# tractor_2v3.net
KiCad netlist of a schematic drawn in EAGLE
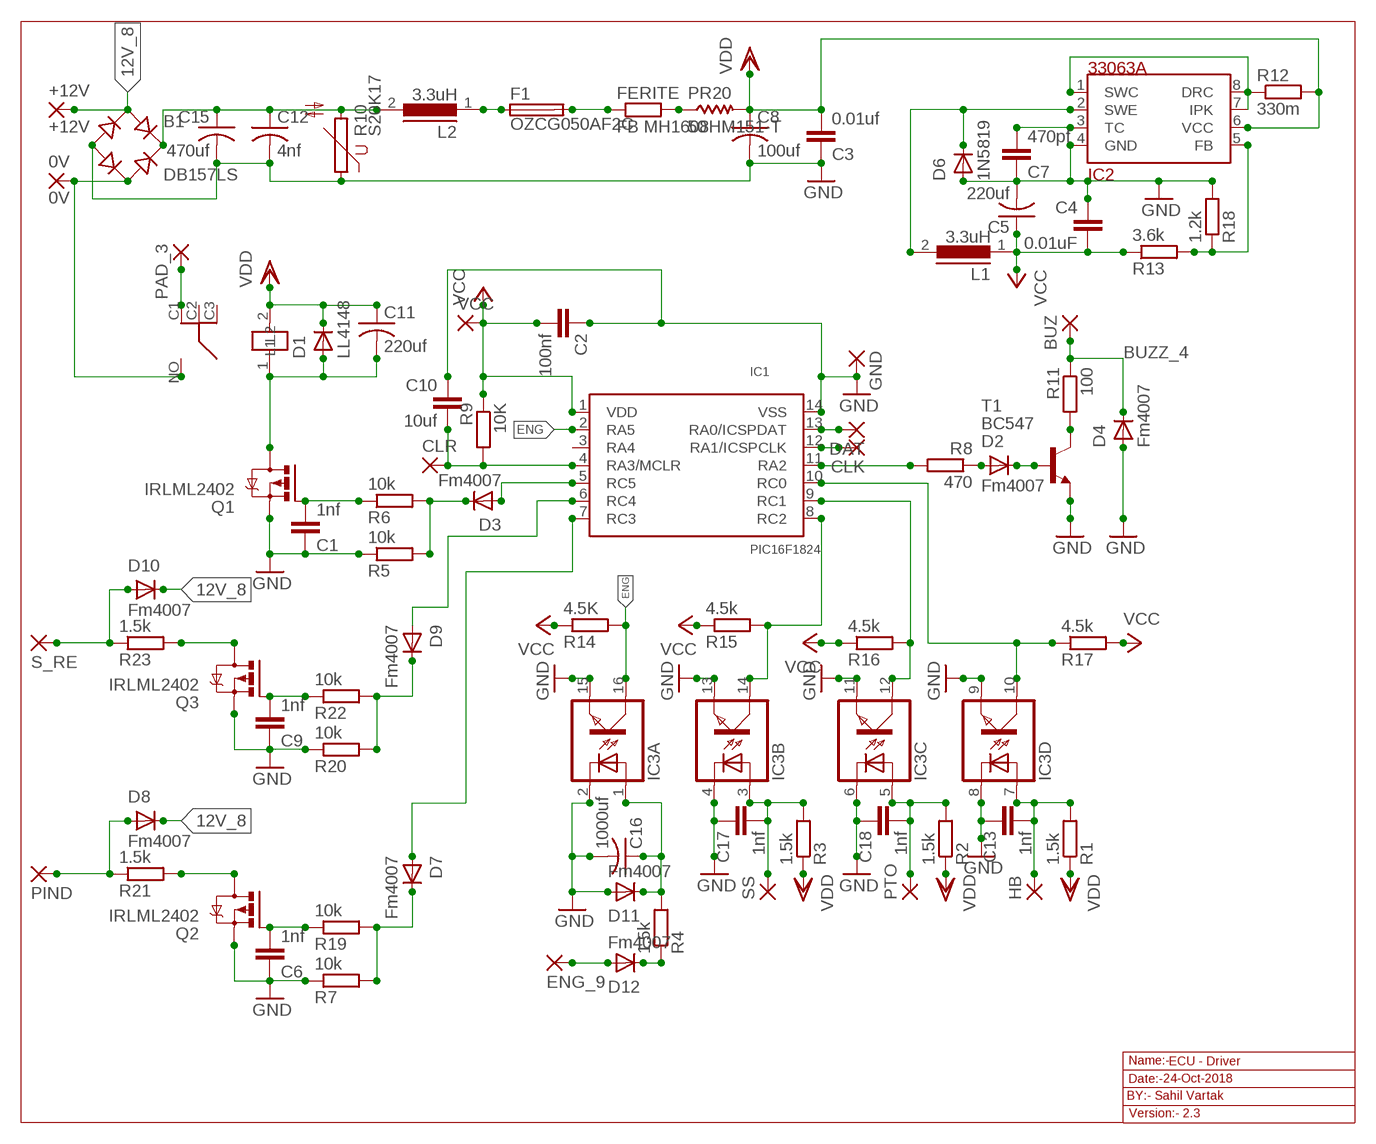
[diagram p0: schematic, sheet 1]

(export (version "E")
  (design (tool "Eeschema 10.0.6"))
  (components
    (comp (ref "+12V")
      (value "+12V")
      (footprint "eagle-import:2,54_1,1")
      (libsource (lib "eagle-import") (part "2,54/1,1"))
    )
    (comp (ref "0V")
      (value "0V")
      (footprint "eagle-import:2,54_1,1")
      (libsource (lib "eagle-import") (part "2,54/1,1"))
    )
    (comp (ref "B1")
      (value "DB157LS")
      (footprint "eagle-import:DBS")
      (libsource (lib "eagle-import") (part "DB?GS106"))
    )
    (comp (ref "BUZ")
      (value "2,54/1,1")
      (footprint "eagle-import:2,54_1,1")
      (libsource (lib "eagle-import") (part "2,54/1,1"))
    )
    (comp (ref "C1")
      (value "1nf")
      (footprint "eagle-import:C0603")
      (libsource (lib "eagle-import") (part "CC0603"))
    )
    (comp (ref "C2")
      (value "100nf")
      (footprint "eagle-import:C0603")
      (libsource (lib "eagle-import") (part "CC0603"))
    )
    (comp (ref "C3")
      (value "0.01uf")
      (footprint "eagle-import:C0603")
      (libsource (lib "eagle-import") (part "CC0603"))
    )
    (comp (ref "C4")
      (value "0.01uF")
      (footprint "eagle-import:C0603")
      (libsource (lib "eagle-import") (part "CC0603"))
    )
    (comp (ref "C5")
      (value "220uf")
      (footprint "eagle-import:C025-025X050")
      (libsource (lib "eagle-import") (part "C-US025-025X050"))
    )
    (comp (ref "C6")
      (value "1nf")
      (footprint "eagle-import:C0603")
      (libsource (lib "eagle-import") (part "CC0603"))
    )
    (comp (ref "C7")
      (value "470pf")
      (footprint "eagle-import:C0603")
      (libsource (lib "eagle-import") (part "CC0603"))
    )
    (comp (ref "C8")
      (value "100uf")
      (footprint "eagle-import:C025-025X050")
      (libsource (lib "eagle-import") (part "C-US025-025X050"))
    )
    (comp (ref "C9")
      (value "1nf")
      (footprint "eagle-import:C0603")
      (libsource (lib "eagle-import") (part "CC0603"))
    )
    (comp (ref "C10")
      (value "10uf")
      (footprint "eagle-import:C0603")
      (libsource (lib "eagle-import") (part "CC0603"))
    )
    (comp (ref "C11")
      (value "220uf")
      (footprint "eagle-import:C025-025X050")
      (libsource (lib "eagle-import") (part "C-US025-025X050"))
    )
    (comp (ref "C12")
      (value "4nf")
      (footprint "eagle-import:C050-045X075")
      (libsource (lib "eagle-import") (part "C-US050-045X075"))
    )
    (comp (ref "C13")
      (value "1nf")
      (footprint "eagle-import:C0603")
      (libsource (lib "eagle-import") (part "CC0603"))
    )
    (comp (ref "C15")
      (value "470uf")
      (footprint "eagle-import:C050-075X075")
      (libsource (lib "eagle-import") (part "resistor_C-US050-075X075"))
    )
    (comp (ref "C16")
      (value "1000uf")
      (footprint "eagle-import:C050-075X075")
      (libsource (lib "eagle-import") (part "resistor_C-US050-075X075"))
    )
    (comp (ref "C17")
      (value "1nf")
      (footprint "eagle-import:C0603")
      (libsource (lib "eagle-import") (part "CC0603"))
    )
    (comp (ref "C18")
      (value "1nf")
      (footprint "eagle-import:C0603")
      (libsource (lib "eagle-import") (part "CC0603"))
    )
    (comp (ref "CLK")
      (value "1,6/0,8")
      (footprint "eagle-import:1,6_0,8")
      (libsource (lib "eagle-import") (part "1,6/0,8"))
    )
    (comp (ref "CLR")
      (value "1,6/0,8")
      (footprint "eagle-import:1,6_0,8")
      (libsource (lib "eagle-import") (part "1,6/0,8"))
    )
    (comp (ref "D1")
      (value "LL4148")
      (footprint "eagle-import:SMA-DO214AC")
      (libsource (lib "eagle-import") (part "GF1"))
    )
    (comp (ref "D2")
      (value "Fm4007")
      (footprint "eagle-import:SMA-DO214AC")
      (libsource (lib "eagle-import") (part "GF1"))
    )
    (comp (ref "D3")
      (value "Fm4007")
      (footprint "eagle-import:SMA-DO214AC")
      (libsource (lib "eagle-import") (part "GF1"))
    )
    (comp (ref "D4")
      (value "Fm4007")
      (footprint "eagle-import:SMA-DO214AC")
      (libsource (lib "eagle-import") (part "GF1"))
    )
    (comp (ref "D6")
      (value "1N5819")
      (footprint "eagle-import:SMA-DO214AC")
      (libsource (lib "eagle-import") (part "GF1"))
    )
    (comp (ref "D7")
      (value "Fm4007")
      (footprint "eagle-import:SMA-DO214AC")
      (libsource (lib "eagle-import") (part "GF1"))
    )
    (comp (ref "D8")
      (value "Fm4007")
      (footprint "eagle-import:SMA-DO214AC")
      (libsource (lib "eagle-import") (part "GF1"))
    )
    (comp (ref "D9")
      (value "Fm4007")
      (footprint "eagle-import:SMA-DO214AC")
      (libsource (lib "eagle-import") (part "GF1"))
    )
    (comp (ref "D10")
      (value "Fm4007")
      (footprint "eagle-import:SMA-DO214AC")
      (libsource (lib "eagle-import") (part "GF1"))
    )
    (comp (ref "D11")
      (value "Fm4007")
      (footprint "eagle-import:SMA-DO214AC")
      (libsource (lib "eagle-import") (part "GF1"))
    )
    (comp (ref "D12")
      (value "Fm4007")
      (footprint "eagle-import:SMA-DO214AC")
      (libsource (lib "eagle-import") (part "GF1"))
    )
    (comp (ref "DAT")
      (value "1,6/0,8")
      (footprint "eagle-import:1,6_0,8")
      (libsource (lib "eagle-import") (part "1,6/0,8"))
    )
    (comp (ref "ENG_9")
      (value "2,54/1,1")
      (footprint "eagle-import:2,54_1,1")
      (libsource (lib "eagle-import") (part "2,54/1,1"))
    )
    (comp (ref "F1")
      (value "OZCG050AF2C")
      (footprint "eagle-import:RES_FUSE")
      (libsource (lib "eagle-import") (part "RES_FUSE"))
    )
    (comp (ref "FERITE")
      (value "FB MH1608HM151-T")
      (footprint "eagle-import:R0603")
      (libsource (lib "eagle-import") (part "R-EU_R0603"))
    )
    (comp (ref "GND")
      (value "1,6/0,8")
      (footprint "eagle-import:1,6_0,8")
      (libsource (lib "eagle-import") (part "1,6/0,8"))
    )
    (comp (ref "HB")
      (value "2,54/1,1")
      (footprint "eagle-import:2,54_1,1")
      (libsource (lib "eagle-import") (part "2,54/1,1"))
    )
    (comp (ref "IC1")
      (value "PIC16F1824")
      (footprint "eagle-import:SO-14")
      (libsource (lib "eagle-import") (part "PIC16F1824"))
    )
    (comp (ref "IC2")
      (value "33063A")
      (footprint "eagle-import:D_R-PDSO-G8")
      (libsource (lib "eagle-import") (part "33063A"))
    )
    (comp (ref "IC3")
      (value "TLP283-4")
      (footprint "eagle-import:MINI-FLAT-16")
      (libsource (lib "eagle-import") (part "TLP283-4"))
    )
    (comp (ref "K2")
      (value "RL703")
      (footprint "eagle-import:RL703")
      (libsource (lib "eagle-import") (part "RL703"))
    )
    (comp (ref "L1")
      (value "3.3uH")
      (footprint "eagle-import:82114R")
      (libsource (lib "eagle-import") (part "82114R"))
    )
    (comp (ref "L2")
      (value "3.3uH")
      (footprint "eagle-import:82114R")
      (libsource (lib "eagle-import") (part "82114R"))
    )
    (comp (ref "PAD_3")
      (value "2,54/1,1")
      (footprint "eagle-import:2,54_1,1")
      (libsource (lib "eagle-import") (part "2,54/1,1"))
    )
    (comp (ref "PIND")
      (value "2,54/1,1")
      (footprint "eagle-import:2,54_1,1")
      (libsource (lib "eagle-import") (part "2,54/1,1"))
    )
    (comp (ref "PR20")
      (value "50")
      (footprint "eagle-import:WSC2515")
      (libsource (lib "eagle-import") (part "R-US_WSC2515"))
    )
    (comp (ref "PTO")
      (value "2,54/1,1")
      (footprint "eagle-import:2,54_1,1")
      (libsource (lib "eagle-import") (part "2,54/1,1"))
    )
    (comp (ref "Q1")
      (value "IRLML2402")
      (footprint "eagle-import:MICRO3")
      (libsource (lib "eagle-import") (part "IRLML5203"))
    )
    (comp (ref "Q2")
      (value "IRLML2402")
      (footprint "eagle-import:MICRO3")
      (libsource (lib "eagle-import") (part "IRLML5203"))
    )
    (comp (ref "Q3")
      (value "IRLML2402")
      (footprint "eagle-import:MICRO3")
      (libsource (lib "eagle-import") (part "IRLML5203"))
    )
    (comp (ref "R1")
      (value "1.5k")
      (footprint "eagle-import:R0603")
      (libsource (lib "eagle-import") (part "RR0603"))
    )
    (comp (ref "R2")
      (value "1.5k")
      (footprint "eagle-import:R0603")
      (libsource (lib "eagle-import") (part "RR0603"))
    )
    (comp (ref "R3")
      (value "1.5k")
      (footprint "eagle-import:R0603")
      (libsource (lib "eagle-import") (part "RR0603"))
    )
    (comp (ref "R4")
      (value "1.5k")
      (footprint "eagle-import:R0603")
      (libsource (lib "eagle-import") (part "RR0603"))
    )
    (comp (ref "R5")
      (value "10k")
      (footprint "eagle-import:R0603")
      (libsource (lib "eagle-import") (part "RR0603"))
    )
    (comp (ref "R6")
      (value "10k")
      (footprint "eagle-import:R0603")
      (libsource (lib "eagle-import") (part "RR0603"))
    )
    (comp (ref "R7")
      (value "10k")
      (footprint "eagle-import:R0603")
      (libsource (lib "eagle-import") (part "RR0603"))
    )
    (comp (ref "R8")
      (value "470")
      (footprint "eagle-import:R0603")
      (libsource (lib "eagle-import") (part "RR0603"))
    )
    (comp (ref "R9")
      (value "10K")
      (footprint "eagle-import:R0603")
      (libsource (lib "eagle-import") (part "RR0603"))
    )
    (comp (ref "R10")
      (value "S20K17")
      (footprint "eagle-import:S14K17")
      (libsource (lib "eagle-import") (part "S14K17"))
    )
    (comp (ref "R11")
      (value "100")
      (footprint "eagle-import:R0603")
      (libsource (lib "eagle-import") (part "RR0603"))
    )
    (comp (ref "R12")
      (value "330m")
      (footprint "eagle-import:R3216")
      (libsource (lib "eagle-import") (part "eagle-ltspice_217_RR3216"))
    )
    (comp (ref "R13")
      (value "3.6k")
      (footprint "eagle-import:R0603")
      (libsource (lib "eagle-import") (part "RR0603"))
    )
    (comp (ref "R14")
      (value "4.5K")
      (footprint "eagle-import:R0603")
      (libsource (lib "eagle-import") (part "RR0603"))
    )
    (comp (ref "R15")
      (value "4.5k")
      (footprint "eagle-import:R0603")
      (libsource (lib "eagle-import") (part "RR0603"))
    )
    (comp (ref "R16")
      (value "4.5k")
      (footprint "eagle-import:R0603")
      (libsource (lib "eagle-import") (part "RR0603"))
    )
    (comp (ref "R17")
      (value "4.5k")
      (footprint "eagle-import:R0603")
      (libsource (lib "eagle-import") (part "RR0603"))
    )
    (comp (ref "R18")
      (value "1.2k")
      (footprint "eagle-import:R0603")
      (libsource (lib "eagle-import") (part "RR0603"))
    )
    (comp (ref "R19")
      (value "10k")
      (footprint "eagle-import:R0603")
      (libsource (lib "eagle-import") (part "RR0603"))
    )
    (comp (ref "R20")
      (value "10k")
      (footprint "eagle-import:R0603")
      (libsource (lib "eagle-import") (part "RR0603"))
    )
    (comp (ref "R21")
      (value "1.5k")
      (footprint "eagle-import:R0603")
      (libsource (lib "eagle-import") (part "RR0603"))
    )
    (comp (ref "R22")
      (value "10k")
      (footprint "eagle-import:R0603")
      (libsource (lib "eagle-import") (part "RR0603"))
    )
    (comp (ref "R23")
      (value "1.5k")
      (footprint "eagle-import:R0603")
      (libsource (lib "eagle-import") (part "RR0603"))
    )
    (comp (ref "SS")
      (value "2,54/1,1")
      (footprint "eagle-import:2,54_1,1")
      (libsource (lib "eagle-import") (part "2,54/1,1"))
    )
    (comp (ref "S_RE")
      (value "2,54/1,1")
      (footprint "eagle-import:2,54_1,1")
      (libsource (lib "eagle-import") (part "2,54/1,1"))
    )
    (comp (ref "T1")
      (value "BC547")
      (footprint "eagle-import:TO92")
      (libsource (lib "eagle-import") (part "BC547"))
    )
    (comp (ref "VCC")
      (value "1,6/0,8")
      (footprint "eagle-import:1,6_0,8")
      (libsource (lib "eagle-import") (part "1,6/0,8"))
    )
  )
  (nets
    (net (code "1") (name "/BUZZ_4") (class "Default")
      (node (ref "BUZ") (pin "1") (pinfunction "P_1") (pintype "passive"))
      (node (ref "D4") (pin "K") (pinfunction "C_K") (pintype "passive"))
      (node (ref "R11") (pin "1") (pinfunction "1_1") (pintype "passive"))
    )
    (net (code "2") (name "12V_8") (class "Default")
      (node (ref "+12V") (pin "1") (pinfunction "P_1") (pintype "passive"))
      (node (ref "B1") (pin "AC1") (pinfunction "AC1_AC1") (pintype "passive"))
      (node (ref "D10") (pin "K") (pinfunction "C_K") (pintype "passive"))
      (node (ref "D8") (pin "K") (pinfunction "C_K") (pintype "passive"))
    )
    (net (code "3") (name "ENG") (class "Default")
      (node (ref "IC1") (pin "2") (pinfunction "RA5_2") (pintype "bidirectional"))
      (node (ref "IC3") (pin "16") (pinfunction "COL_16") (pintype "passive"))
      (node (ref "R14") (pin "2") (pinfunction "2_2") (pintype "passive"))
    )
    (net (code "4") (name "GND") (class "Default")
      (node (ref "B1") (pin "-") (pinfunction "-_-") (pintype "passive"))
      (node (ref "C1") (pin "1") (pinfunction "1_1") (pintype "passive"))
      (node (ref "C10") (pin "1") (pinfunction "1_1") (pintype "passive"))
      (node (ref "C12") (pin "2") (pinfunction "2_2") (pintype "passive"))
      (node (ref "C13") (pin "1") (pinfunction "1_1") (pintype "passive"))
      (node (ref "C15") (pin "2") (pinfunction "2_2") (pintype "passive"))
      (node (ref "C16") (pin "2") (pinfunction "2_2") (pintype "passive"))
      (node (ref "C17") (pin "1") (pinfunction "1_1") (pintype "passive"))
      (node (ref "C18") (pin "1") (pinfunction "1_1") (pintype "passive"))
      (node (ref "C2") (pin "1") (pinfunction "1_1") (pintype "passive"))
      (node (ref "C3") (pin "1") (pinfunction "1_1") (pintype "passive"))
      (node (ref "C4") (pin "1") (pinfunction "1_1") (pintype "passive"))
      (node (ref "C5") (pin "2") (pinfunction "2_2") (pintype "passive"))
      (node (ref "C6") (pin "1") (pinfunction "1_1") (pintype "passive"))
      (node (ref "C7") (pin "1") (pinfunction "1_1") (pintype "passive"))
      (node (ref "C8") (pin "2") (pinfunction "2_2") (pintype "passive"))
      (node (ref "C9") (pin "1") (pinfunction "1_1") (pintype "passive"))
      (node (ref "D11") (pin "A") (pinfunction "A_A") (pintype "passive"))
      (node (ref "D4") (pin "A") (pinfunction "A_A") (pintype "passive"))
      (node (ref "D6") (pin "A") (pinfunction "A_A") (pintype "passive"))
      (node (ref "GND") (pin "1") (pinfunction "P_1") (pintype "passive"))
      (node (ref "IC1") (pin "14") (pinfunction "VSS_14") (pintype "bidirectional"))
      (node (ref "IC2") (pin "4") (pinfunction "GND_4") (pintype "bidirectional"))
      (node (ref "IC3") (pin "11") (pinfunction "EMIT_11") (pintype "passive"))
      (node (ref "IC3") (pin "13") (pinfunction "EMIT_13") (pintype "passive"))
      (node (ref "IC3") (pin "15") (pinfunction "EMIT_15") (pintype "passive"))
      (node (ref "IC3") (pin "2") (pinfunction "C_2") (pintype "passive"))
      (node (ref "IC3") (pin "4") (pinfunction "C_4") (pintype "passive"))
      (node (ref "IC3") (pin "6") (pinfunction "C_6") (pintype "passive"))
      (node (ref "IC3") (pin "8") (pinfunction "C_8") (pintype "passive"))
      (node (ref "IC3") (pin "9") (pinfunction "EMIT_9") (pintype "passive"))
      (node (ref "Q1") (pin "2") (pinfunction "S_2") (pintype "passive"))
      (node (ref "Q2") (pin "2") (pinfunction "S_2") (pintype "passive"))
      (node (ref "Q3") (pin "2") (pinfunction "S_2") (pintype "passive"))
      (node (ref "R10") (pin "1") (pinfunction "1_1") (pintype "passive"))
      (node (ref "R18") (pin "2") (pinfunction "2_2") (pintype "passive"))
      (node (ref "R20") (pin "1") (pinfunction "1_1") (pintype "passive"))
      (node (ref "R5") (pin "1") (pinfunction "1_1") (pintype "passive"))
      (node (ref "R7") (pin "1") (pinfunction "1_1") (pintype "passive"))
      (node (ref "T1") (pin "1") (pinfunction "E_1") (pintype "passive"))
    )
    (net (code "5") (name "Net-(0V-P)") (class "Default")
      (node (ref "0V") (pin "1") (pinfunction "P_1") (pintype "passive"))
      (node (ref "B1") (pin "AC2") (pinfunction "AC2_AC2") (pintype "passive"))
      (node (ref "K2") (pin "NO") (pinfunction "NO_NO") (pintype "bidirectional"))
    )
    (net (code "6") (name "Net-(B1-Pad+)") (class "Default")
      (node (ref "B1") (pin "+") (pinfunction "+_+") (pintype "passive"))
      (node (ref "C12") (pin "1") (pinfunction "1_1") (pintype "passive"))
      (node (ref "C15") (pin "1") (pinfunction "1_1") (pintype "passive"))
      (node (ref "L2") (pin "2") (pinfunction "2_2") (pintype "passive"))
      (node (ref "R10") (pin "2") (pinfunction "2_2") (pintype "passive"))
    )
    (net (code "7") (name "Net-(CLK-P)") (class "Default")
      (node (ref "CLK") (pin "1") (pinfunction "P_1") (pintype "passive"))
      (node (ref "IC1") (pin "12") (pinfunction "RA1/ICSPCLK_12") (pintype "bidirectional"))
    )
    (net (code "8") (name "Net-(CLR-P)") (class "Default")
      (node (ref "C10") (pin "2") (pinfunction "2_2") (pintype "passive"))
      (node (ref "CLR") (pin "1") (pinfunction "P_1") (pintype "passive"))
      (node (ref "IC1") (pin "4") (pinfunction "RA3/MCLR_4") (pintype "bidirectional"))
      (node (ref "R9") (pin "2") (pinfunction "2_2") (pintype "passive"))
    )
    (net (code "9") (name "Net-(D2-C)") (class "Default")
      (node (ref "D2") (pin "K") (pinfunction "C_K") (pintype "passive"))
      (node (ref "T1") (pin "2") (pinfunction "B_2") (pintype "passive"))
    )
    (net (code "10") (name "Net-(D2-PadA)") (class "Default")
      (node (ref "D2") (pin "A") (pinfunction "A_A") (pintype "passive"))
      (node (ref "R8") (pin "1") (pinfunction "1_1") (pintype "passive"))
    )
    (net (code "11") (name "Net-(D3-C)") (class "Default")
      (node (ref "D3") (pin "K") (pinfunction "C_K") (pintype "passive"))
      (node (ref "R5") (pin "2") (pinfunction "2_2") (pintype "passive"))
      (node (ref "R6") (pin "2") (pinfunction "2_2") (pintype "passive"))
    )
    (net (code "12") (name "Net-(D6-C)") (class "Default")
      (node (ref "D6") (pin "K") (pinfunction "C_K") (pintype "passive"))
      (node (ref "IC2") (pin "2") (pinfunction "SWE_2") (pintype "bidirectional"))
      (node (ref "L1") (pin "2") (pinfunction "2_2") (pintype "passive"))
    )
    (net (code "13") (name "Net-(D7-C)") (class "Default")
      (node (ref "D7") (pin "K") (pinfunction "C_K") (pintype "passive"))
      (node (ref "R19") (pin "2") (pinfunction "2_2") (pintype "passive"))
      (node (ref "R7") (pin "2") (pinfunction "2_2") (pintype "passive"))
    )
    (net (code "14") (name "Net-(D9-C)") (class "Default")
      (node (ref "D9") (pin "K") (pinfunction "C_K") (pintype "passive"))
      (node (ref "R20") (pin "2") (pinfunction "2_2") (pintype "passive"))
      (node (ref "R22") (pin "2") (pinfunction "2_2") (pintype "passive"))
    )
    (net (code "15") (name "Net-(D11-C)") (class "Default")
      (node (ref "C16") (pin "1") (pinfunction "1_1") (pintype "passive"))
      (node (ref "D11") (pin "K") (pinfunction "C_K") (pintype "passive"))
      (node (ref "IC3") (pin "1") (pinfunction "A_1") (pintype "passive"))
      (node (ref "R4") (pin "2") (pinfunction "2_2") (pintype "passive"))
    )
    (net (code "16") (name "Net-(D12-C)") (class "Default")
      (node (ref "D12") (pin "K") (pinfunction "C_K") (pintype "passive"))
      (node (ref "R4") (pin "1") (pinfunction "1_1") (pintype "passive"))
    )
    (net (code "17") (name "Net-(DAT-P)") (class "Default")
      (node (ref "DAT") (pin "1") (pinfunction "P_1") (pintype "passive"))
      (node (ref "IC1") (pin "13") (pinfunction "RA0/ICSPDAT_13") (pintype "bidirectional"))
    )
    (net (code "18") (name "Net-(ENG_9-P)") (class "Default")
      (node (ref "D12") (pin "A") (pinfunction "A_A") (pintype "passive"))
      (node (ref "ENG_9") (pin "1") (pinfunction "P_1") (pintype "passive"))
    )
    (net (code "19") (name "Net-(F1-3)") (class "Default")
      (node (ref "F1") (pin "1") (pinfunction "3_1") (pintype "passive"))
      (node (ref "L2") (pin "1") (pinfunction "1_1") (pintype "passive"))
    )
    (net (code "20") (name "Net-(F1-4)") (class "Default")
      (node (ref "F1") (pin "2") (pinfunction "4_2") (pintype "passive"))
      (node (ref "FERITE") (pin "1") (pinfunction "1_1") (pintype "passive"))
    )
    (net (code "21") (name "Net-(FERITE-Pad2)") (class "Default")
      (node (ref "FERITE") (pin "2") (pinfunction "2_2") (pintype "passive"))
      (node (ref "PR20") (pin "1") (pinfunction "1_1") (pintype "passive"))
    )
    (net (code "22") (name "Net-(HB-P)") (class "Default")
      (node (ref "C13") (pin "2") (pinfunction "2_2") (pintype "passive"))
      (node (ref "HB") (pin "1") (pinfunction "P_1") (pintype "passive"))
      (node (ref "IC3") (pin "7") (pinfunction "A_7") (pintype "passive"))
      (node (ref "R1") (pin "2") (pinfunction "2_2") (pintype "passive"))
    )
    (net (code "23") (name "Net-(IC1-RA2)") (class "Default")
      (node (ref "IC1") (pin "11") (pinfunction "RA2_11") (pintype "bidirectional"))
      (node (ref "R8") (pin "2") (pinfunction "2_2") (pintype "passive"))
    )
    (net (code "24") (name "Net-(IC1-RC0)") (class "Default")
      (node (ref "IC1") (pin "10") (pinfunction "RC0_10") (pintype "bidirectional"))
      (node (ref "IC3") (pin "10") (pinfunction "COL_10") (pintype "passive"))
      (node (ref "R17") (pin "1") (pinfunction "1_1") (pintype "passive"))
    )
    (net (code "25") (name "Net-(IC1-RC1)") (class "Default")
      (node (ref "IC1") (pin "9") (pinfunction "RC1_9") (pintype "bidirectional"))
      (node (ref "IC3") (pin "12") (pinfunction "COL_12") (pintype "passive"))
      (node (ref "R16") (pin "2") (pinfunction "2_2") (pintype "passive"))
    )
    (net (code "26") (name "Net-(IC1-RC2)") (class "Default")
      (node (ref "IC1") (pin "8") (pinfunction "RC2_8") (pintype "bidirectional"))
      (node (ref "IC3") (pin "14") (pinfunction "COL_14") (pintype "passive"))
      (node (ref "R15") (pin "2") (pinfunction "2_2") (pintype "passive"))
    )
    (net (code "27") (name "Net-(IC1-RC3)") (class "Default")
      (node (ref "D7") (pin "A") (pinfunction "A_A") (pintype "passive"))
      (node (ref "IC1") (pin "7") (pinfunction "RC3_7") (pintype "bidirectional"))
    )
    (net (code "28") (name "Net-(IC1-RC4)") (class "Default")
      (node (ref "D9") (pin "A") (pinfunction "A_A") (pintype "passive"))
      (node (ref "IC1") (pin "6") (pinfunction "RC4_6") (pintype "bidirectional"))
    )
    (net (code "29") (name "Net-(IC1-RC5)") (class "Default")
      (node (ref "D3") (pin "A") (pinfunction "A_A") (pintype "passive"))
      (node (ref "IC1") (pin "5") (pinfunction "RC5_5") (pintype "bidirectional"))
    )
    (net (code "30") (name "Net-(IC2-DRC)") (class "Default")
      (node (ref "IC2") (pin "1") (pinfunction "SWC_1") (pintype "bidirectional"))
      (node (ref "IC2") (pin "7") (pinfunction "IPK_7") (pintype "bidirectional"))
      (node (ref "IC2") (pin "8") (pinfunction "DRC_8") (pintype "bidirectional"))
      (node (ref "R12") (pin "1") (pinfunction "1_1") (pintype "passive"))
    )
    (net (code "31") (name "Net-(IC2-FB)") (class "Default")
      (node (ref "IC2") (pin "5") (pinfunction "FB_5") (pintype "bidirectional"))
      (node (ref "R13") (pin "2") (pinfunction "2_2") (pintype "passive"))
      (node (ref "R18") (pin "1") (pinfunction "1_1") (pintype "passive"))
    )
    (net (code "32") (name "Net-(IC2-TC)") (class "Default")
      (node (ref "C7") (pin "2") (pinfunction "2_2") (pintype "passive"))
      (node (ref "IC2") (pin "3") (pinfunction "TC_3") (pintype "bidirectional"))
    )
    (net (code "33") (name "Net-(IC3B-A)") (class "Default")
      (node (ref "C17") (pin "2") (pinfunction "2_2") (pintype "passive"))
      (node (ref "IC3") (pin "3") (pinfunction "A_3") (pintype "passive"))
      (node (ref "R3") (pin "2") (pinfunction "2_2") (pintype "passive"))
      (node (ref "SS") (pin "1") (pinfunction "P_1") (pintype "passive"))
    )
    (net (code "34") (name "Net-(IC3C-A)") (class "Default")
      (node (ref "C18") (pin "2") (pinfunction "2_2") (pintype "passive"))
      (node (ref "IC3") (pin "5") (pinfunction "A_5") (pintype "passive"))
      (node (ref "PTO") (pin "1") (pinfunction "P_1") (pintype "passive"))
      (node (ref "R2") (pin "2") (pinfunction "2_2") (pintype "passive"))
    )
    (net (code "35") (name "Net-(K2-L2)") (class "Default")
      (node (ref "C11") (pin "2") (pinfunction "2_2") (pintype "passive"))
      (node (ref "D1") (pin "A") (pinfunction "A_A") (pintype "passive"))
      (node (ref "K2") (pin "1") (pinfunction "L2_1") (pintype "bidirectional"))
      (node (ref "Q1") (pin "3") (pinfunction "D_3") (pintype "passive"))
    )
    (net (code "36") (name "Net-(PAD_3-P)") (class "Default")
      (node (ref "K2") (pin "C1") (pinfunction "C1_C1") (pintype "bidirectional"))
      (node (ref "PAD_3") (pin "1") (pinfunction "P_1") (pintype "passive"))
    )
    (net (code "37") (name "Net-(PIND-P)") (class "Default")
      (node (ref "D8") (pin "A") (pinfunction "A_A") (pintype "passive"))
      (node (ref "PIND") (pin "1") (pinfunction "P_1") (pintype "passive"))
      (node (ref "R21") (pin "1") (pinfunction "1_1") (pintype "passive"))
    )
    (net (code "38") (name "Net-(Q1-G)") (class "Default")
      (node (ref "C1") (pin "2") (pinfunction "2_2") (pintype "passive"))
      (node (ref "Q1") (pin "1") (pinfunction "G_1") (pintype "passive"))
      (node (ref "R6") (pin "1") (pinfunction "1_1") (pintype "passive"))
    )
    (net (code "39") (name "Net-(Q2-D)") (class "Default")
      (node (ref "Q2") (pin "3") (pinfunction "D_3") (pintype "passive"))
      (node (ref "R21") (pin "2") (pinfunction "2_2") (pintype "passive"))
    )
    (net (code "40") (name "Net-(Q2-G)") (class "Default")
      (node (ref "C6") (pin "2") (pinfunction "2_2") (pintype "passive"))
      (node (ref "Q2") (pin "1") (pinfunction "G_1") (pintype "passive"))
      (node (ref "R19") (pin "1") (pinfunction "1_1") (pintype "passive"))
    )
    (net (code "41") (name "Net-(Q3-D)") (class "Default")
      (node (ref "Q3") (pin "3") (pinfunction "D_3") (pintype "passive"))
      (node (ref "R23") (pin "2") (pinfunction "2_2") (pintype "passive"))
    )
    (net (code "42") (name "Net-(Q3-G)") (class "Default")
      (node (ref "C9") (pin "2") (pinfunction "2_2") (pintype "passive"))
      (node (ref "Q3") (pin "1") (pinfunction "G_1") (pintype "passive"))
      (node (ref "R22") (pin "1") (pinfunction "1_1") (pintype "passive"))
    )
    (net (code "43") (name "Net-(S_RE-P)") (class "Default")
      (node (ref "D10") (pin "A") (pinfunction "A_A") (pintype "passive"))
      (node (ref "R23") (pin "1") (pinfunction "1_1") (pintype "passive"))
      (node (ref "S_RE") (pin "1") (pinfunction "P_1") (pintype "passive"))
    )
    (net (code "44") (name "Net-(T1-C)") (class "Default")
      (node (ref "R11") (pin "2") (pinfunction "2_2") (pintype "passive"))
      (node (ref "T1") (pin "3") (pinfunction "C_3") (pintype "passive"))
    )
    (net (code "45") (name "VCC") (class "Default")
      (node (ref "C2") (pin "2") (pinfunction "2_2") (pintype "passive"))
      (node (ref "C4") (pin "2") (pinfunction "2_2") (pintype "passive"))
      (node (ref "C5") (pin "1") (pinfunction "1_1") (pintype "passive"))
      (node (ref "IC1") (pin "1") (pinfunction "VDD_1") (pintype "bidirectional"))
      (node (ref "L1") (pin "1") (pinfunction "1_1") (pintype "passive"))
      (node (ref "R13") (pin "1") (pinfunction "1_1") (pintype "passive"))
      (node (ref "R14") (pin "1") (pinfunction "1_1") (pintype "passive"))
      (node (ref "R15") (pin "1") (pinfunction "1_1") (pintype "passive"))
      (node (ref "R16") (pin "1") (pinfunction "1_1") (pintype "passive"))
      (node (ref "R17") (pin "2") (pinfunction "2_2") (pintype "passive"))
      (node (ref "R9") (pin "1") (pinfunction "1_1") (pintype "passive"))
      (node (ref "VCC") (pin "1") (pinfunction "P_1") (pintype "passive"))
    )
    (net (code "46") (name "VDD") (class "Default")
      (node (ref "C11") (pin "1") (pinfunction "1_1") (pintype "passive"))
      (node (ref "C3") (pin "2") (pinfunction "2_2") (pintype "passive"))
      (node (ref "C8") (pin "1") (pinfunction "1_1") (pintype "passive"))
      (node (ref "D1") (pin "K") (pinfunction "C_K") (pintype "passive"))
      (node (ref "IC2") (pin "6") (pinfunction "VCC_6") (pintype "bidirectional"))
      (node (ref "K2") (pin "2") (pinfunction "L1_2") (pintype "bidirectional"))
      (node (ref "PR20") (pin "2") (pinfunction "2_2") (pintype "passive"))
      (node (ref "R1") (pin "1") (pinfunction "1_1") (pintype "passive"))
      (node (ref "R12") (pin "2") (pinfunction "2_2") (pintype "passive"))
      (node (ref "R2") (pin "1") (pinfunction "1_1") (pintype "passive"))
      (node (ref "R3") (pin "1") (pinfunction "1_1") (pintype "passive"))
    )
    (net (code "47") (name "unconnected-(IC1-RA4-Pad3)") (class "Default")
      (node (ref "IC1") (pin "3") (pinfunction "RA4_3") (pintype "bidirectional"))
    )
    (net (code "48") (name "unconnected-(K2-PadC2)") (class "Default")
      (node (ref "K2") (pin "C2") (pinfunction "C2_C2") (pintype "bidirectional"))
    )
    (net (code "49") (name "unconnected-(K2-PadC3)") (class "Default")
      (node (ref "K2") (pin "C3") (pinfunction "C3_C3") (pintype "bidirectional"))
    )
  )
)
